# SignalConditioningShield.net
KiCad netlist of a schematic drawn in Altium Designer
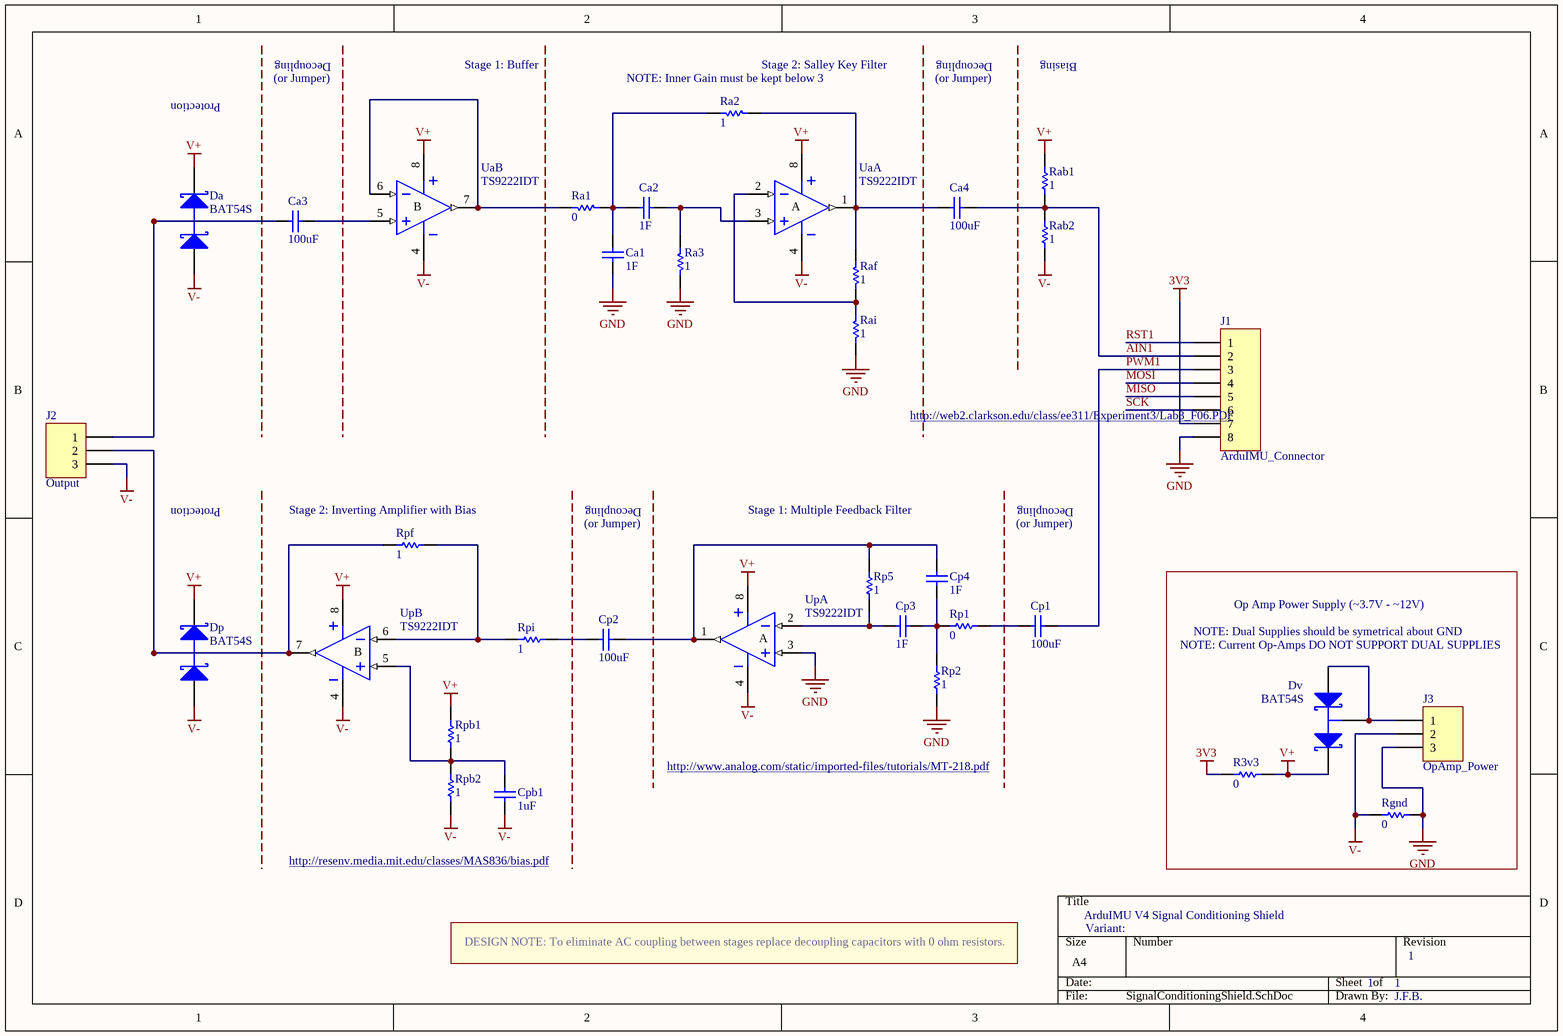
[diagram p0: SignalConditioningShield.SchDoc]

(export (version "E")
  (design (tool "Eeschema 10.0.6"))
  (components
    (comp (ref "Ca1")
      (value "1F")
      (footprint "8-1206")
      (description "Capacitor (Semiconductor SIM Model)")
      (fields (field (name "Comment") "Cap Semi") (field (name "PUBLISHER") "Altium Limited"))
      (libsource (lib "Miscellaneous Devices") (part "Cap Semi"))
    )
    (comp (ref "Ca2")
      (value "1F")
      (footprint "8-1206")
      (description "Capacitor (Semiconductor SIM Model)")
      (fields (field (name "Comment") "Cap Semi") (field (name "PUBLISHER") "Altium Limited"))
      (libsource (lib "Miscellaneous Devices") (part "Cap Semi"))
    )
    (comp (ref "Ca3")
      (value "100uF")
      (footprint "8-1206")
      (description "Capacitor (Semiconductor SIM Model)")
      (fields (field (name "Comment") "Cap Semi") (field (name "PUBLISHER") "Altium Limited"))
      (libsource (lib "Miscellaneous Devices") (part "Cap Semi"))
    )
    (comp (ref "Ca4")
      (value "100uF")
      (footprint "8-1206")
      (description "Capacitor (Semiconductor SIM Model)")
      (fields (field (name "Comment") "Cap Semi") (field (name "PUBLISHER") "Altium Limited"))
      (libsource (lib "Miscellaneous Devices") (part "Cap Semi"))
    )
    (comp (ref "Cp1")
      (value "100uF")
      (footprint "8-1206")
      (description "Capacitor (Semiconductor SIM Model)")
      (fields (field (name "Comment") "Cap Semi") (field (name "PUBLISHER") "Altium Limited"))
      (libsource (lib "Miscellaneous Devices") (part "Cap Semi"))
    )
    (comp (ref "Cp2")
      (value "100uF")
      (footprint "8-1206")
      (description "Capacitor (Semiconductor SIM Model)")
      (fields (field (name "Comment") "Cap Semi") (field (name "PUBLISHER") "Altium Limited"))
      (libsource (lib "Miscellaneous Devices") (part "Cap Semi"))
    )
    (comp (ref "Cp3")
      (value "1F")
      (footprint "8-1206")
      (description "Capacitor (Semiconductor SIM Model)")
      (fields (field (name "Comment") "Cap Semi") (field (name "PUBLISHER") "Altium Limited"))
      (libsource (lib "Miscellaneous Devices") (part "Cap Semi"))
    )
    (comp (ref "Cp4")
      (value "1F")
      (footprint "8-1206")
      (description "Capacitor (Semiconductor SIM Model)")
      (fields (field (name "Comment") "Cap Semi") (field (name "PUBLISHER") "Altium Limited"))
      (libsource (lib "Miscellaneous Devices") (part "Cap Semi"))
    )
    (comp (ref "Cpb1")
      (value "1uF")
      (footprint "8-1206")
      (description "Capacitor (Semiconductor SIM Model)")
      (fields (field (name "Comment") "Cap Semi") (field (name "PUBLISHER") "Altium Limited"))
      (libsource (lib "Miscellaneous Devices") (part "Cap Semi"))
    )
    (comp (ref "Da")
      (value "BAT54S")
      (footprint "SOT23_M")
      (description "Schottky Barrier Double Diode")
      (fields (field (name "PUBLISHER") "Altium Limited"))
      (libsource (lib "Philips Discrete Diode - Schottky") (part "BAT54S"))
    )
    (comp (ref "Dp")
      (value "BAT54S")
      (footprint "SOT23_M")
      (description "Schottky Barrier Double Diode")
      (fields (field (name "PUBLISHER") "Altium Limited"))
      (libsource (lib "Philips Discrete Diode - Schottky") (part "BAT54S"))
    )
    (comp (ref "Dv")
      (value "BAT54S")
      (footprint "SOT23_M")
      (description "Schottky Barrier Double Diode")
      (fields (field (name "PUBLISHER") "Altium Limited"))
      (libsource (lib "Philips Discrete Diode - Schottky") (part "BAT54S"))
    )
    (comp (ref "J1")
      (value "ArduIMU_Connector")
      (footprint "HDR1X8")
      (description "Header, 8-Pin")
      (fields (field (name "PUBLISHER") "Altium Limited"))
      (libsource (lib "Miscellaneous Connectors") (part "Header 8"))
    )
    (comp (ref "J2")
      (value "Output")
      (footprint "HDR1X3")
      (description "Header, 3-Pin")
      (fields (field (name "PUBLISHER") "Altium Limited"))
      (libsource (lib "Miscellaneous Connectors") (part "Header 3"))
    )
    (comp (ref "J3")
      (value "OpAmp_Power")
      (footprint "HDR1X3")
      (description "Header, 3-Pin")
      (fields (field (name "PUBLISHER") "Altium Limited"))
      (libsource (lib "") (part "Header 3_1"))
    )
    (comp (ref "R3v3")
      (value "0")
      (footprint "6-0805")
      (description "Thick Film Chip Resistor, 1 Ohm to 10M Ohm Range, 5% Tolerance, 0805 Size, 0.125 W")
      (fields (field (name "PUBLISHER") "Altium Limited"))
      (libsource (lib "Panasonic Resistor") (part "ERJ6GE"))
    )
    (comp (ref "Ra1")
      (value "0")
      (footprint "8-1206")
      (description "Precision Thick Film Chip Resistor, 10 Ohm to 2.2M Ohm Range, 1% Tolerance, 1206 Size, 0.125 W")
      (fields (field (name "PUBLISHER") "Altium Limited"))
      (libsource (lib "Panasonic Resistor") (part "ERJ8EN"))
    )
    (comp (ref "Ra2")
      (value "1")
      (footprint "8-1206")
      (description "Precision Thick Film Chip Resistor, 10 Ohm to 2.2M Ohm Range, 1% Tolerance, 1206 Size, 0.125 W")
      (fields (field (name "PUBLISHER") "Altium Limited"))
      (libsource (lib "Panasonic Resistor") (part "ERJ8EN"))
    )
    (comp (ref "Ra3")
      (value "1")
      (footprint "8-1206")
      (description "Precision Thick Film Chip Resistor, 10 Ohm to 2.2M Ohm Range, 1% Tolerance, 1206 Size, 0.125 W")
      (fields (field (name "PUBLISHER") "Altium Limited"))
      (libsource (lib "Panasonic Resistor") (part "ERJ8EN"))
    )
    (comp (ref "Rab1")
      (value "1")
      (footprint "8-1206")
      (description "Precision Thick Film Chip Resistor, 10 Ohm to 2.2M Ohm Range, 1% Tolerance, 1206 Size, 0.125 W")
      (fields (field (name "PUBLISHER") "Altium Limited"))
      (libsource (lib "Panasonic Resistor") (part "ERJ8EN"))
    )
    (comp (ref "Rab2")
      (value "1")
      (footprint "8-1206")
      (description "Precision Thick Film Chip Resistor, 10 Ohm to 2.2M Ohm Range, 1% Tolerance, 1206 Size, 0.125 W")
      (fields (field (name "PUBLISHER") "Altium Limited"))
      (libsource (lib "Panasonic Resistor") (part "ERJ8EN"))
    )
    (comp (ref "Raf")
      (value "1")
      (footprint "8-1206")
      (description "Precision Thick Film Chip Resistor, 10 Ohm to 2.2M Ohm Range, 1% Tolerance, 1206 Size, 0.125 W")
      (fields (field (name "PUBLISHER") "Altium Limited"))
      (libsource (lib "Panasonic Resistor") (part "ERJ8EN"))
    )
    (comp (ref "Rai")
      (value "1")
      (footprint "8-1206")
      (description "Precision Thick Film Chip Resistor, 10 Ohm to 2.2M Ohm Range, 1% Tolerance, 1206 Size, 0.125 W")
      (fields (field (name "PUBLISHER") "Altium Limited"))
      (libsource (lib "Panasonic Resistor") (part "ERJ8EN"))
    )
    (comp (ref "Rgnd")
      (value "0")
      (footprint "6-0805")
      (description "Thick Film Chip Resistor, 1 Ohm to 10M Ohm Range, 5% Tolerance, 0805 Size, 0.125 W")
      (fields (field (name "PUBLISHER") "Altium Limited"))
      (libsource (lib "Panasonic Resistor") (part "ERJ6GE"))
    )
    (comp (ref "Rp1")
      (value "0")
      (footprint "8-1206")
      (description "Precision Thick Film Chip Resistor, 10 Ohm to 2.2M Ohm Range, 1% Tolerance, 1206 Size, 0.125 W")
      (fields (field (name "PUBLISHER") "Altium Limited"))
      (libsource (lib "Panasonic Resistor") (part "ERJ8EN"))
    )
    (comp (ref "Rp2")
      (value "1")
      (footprint "8-1206")
      (description "Precision Thick Film Chip Resistor, 10 Ohm to 2.2M Ohm Range, 1% Tolerance, 1206 Size, 0.125 W")
      (fields (field (name "PUBLISHER") "Altium Limited"))
      (libsource (lib "Panasonic Resistor") (part "ERJ8EN"))
    )
    (comp (ref "Rp5")
      (value "1")
      (footprint "8-1206")
      (description "Precision Thick Film Chip Resistor, 10 Ohm to 2.2M Ohm Range, 1% Tolerance, 1206 Size, 0.125 W")
      (fields (field (name "PUBLISHER") "Altium Limited"))
      (libsource (lib "Panasonic Resistor") (part "ERJ8EN"))
    )
    (comp (ref "Rpb1")
      (value "1")
      (footprint "8-1206")
      (description "Precision Thick Film Chip Resistor, 10 Ohm to 2.2M Ohm Range, 1% Tolerance, 1206 Size, 0.125 W")
      (fields (field (name "PUBLISHER") "Altium Limited"))
      (libsource (lib "Panasonic Resistor") (part "ERJ8EN"))
    )
    (comp (ref "Rpb2")
      (value "1")
      (footprint "8-1206")
      (description "Precision Thick Film Chip Resistor, 10 Ohm to 2.2M Ohm Range, 1% Tolerance, 1206 Size, 0.125 W")
      (fields (field (name "PUBLISHER") "Altium Limited"))
      (libsource (lib "Panasonic Resistor") (part "ERJ8EN"))
    )
    (comp (ref "Rpf")
      (value "1")
      (footprint "8-1206")
      (description "Precision Thick Film Chip Resistor, 10 Ohm to 2.2M Ohm Range, 1% Tolerance, 1206 Size, 0.125 W")
      (fields (field (name "PUBLISHER") "Altium Limited"))
      (libsource (lib "Panasonic Resistor") (part "ERJ8EN"))
    )
    (comp (ref "Rpi")
      (value "1")
      (footprint "8-1206")
      (description "Precision Thick Film Chip Resistor, 10 Ohm to 2.2M Ohm Range, 1% Tolerance, 1206 Size, 0.125 W")
      (fields (field (name "PUBLISHER") "Altium Limited"))
      (libsource (lib "Panasonic Resistor") (part "ERJ8EN"))
    )
    (comp (ref "Ua")
      (value "TS9222IDT")
      (footprint "TSSOP8_L")
      (description "High precision, high stability dual operational amplifier")
      (libsource (lib "SignalConditioningShield") (part "TS9222IDT"))
    )
    (comp (ref "Up")
      (value "TS9222IDT")
      (footprint "TSSOP8_L")
      (description "High precision, high stability dual operational amplifier")
      (libsource (lib "SignalConditioningShield") (part "TS9222IDT"))
    )
  )
  (nets
    (net (code "1") (name "/AIN1") (class "Default")
      (node (ref "Ca4") (pin "1") (pinfunction "1_1") (pintype "passive"))
      (node (ref "J1") (pin "2") (pinfunction "2_2") (pintype "passive"))
      (node (ref "Rab1") (pin "1") (pinfunction "1_1") (pintype "passive"))
      (node (ref "Rab2") (pin "2") (pinfunction "2_2") (pintype "passive"))
    )
    (net (code "2") (name "/MISO") (class "Default")
      (node (ref "J1") (pin "5") (pinfunction "5_5") (pintype "passive"))
    )
    (net (code "3") (name "/MOSI") (class "Default")
      (node (ref "J1") (pin "4") (pinfunction "4_4") (pintype "passive"))
    )
    (net (code "4") (name "/PWM1") (class "Default")
      (node (ref "Cp1") (pin "2") (pinfunction "2_2") (pintype "passive"))
      (node (ref "J1") (pin "3") (pinfunction "3_3") (pintype "passive"))
    )
    (net (code "5") (name "/RST1") (class "Default")
      (node (ref "J1") (pin "1") (pinfunction "1_1") (pintype "passive"))
    )
    (net (code "6") (name "/SCK") (class "Default")
      (node (ref "J1") (pin "6") (pinfunction "6_6") (pintype "passive"))
    )
    (net (code "7") (name "3V3") (class "Default")
      (node (ref "J1") (pin "7") (pinfunction "7_7") (pintype "passive"))
      (node (ref "R3v3") (pin "2") (pinfunction "2_2") (pintype "passive"))
    )
    (net (code "8") (name "GND") (class "Default")
      (node (ref "Ca1") (pin "1") (pinfunction "1_1") (pintype "passive"))
      (node (ref "J1") (pin "8") (pinfunction "8_8") (pintype "passive"))
      (node (ref "J3") (pin "3") (pinfunction "3_3") (pintype "passive"))
      (node (ref "Ra3") (pin "2") (pinfunction "2_2") (pintype "passive"))
      (node (ref "Rai") (pin "2") (pinfunction "2_2") (pintype "passive"))
      (node (ref "Rgnd") (pin "2") (pinfunction "2_2") (pintype "passive"))
      (node (ref "Rp2") (pin "2") (pinfunction "2_2") (pintype "passive"))
      (node (ref "Up") (pin "3") (pinfunction "IN+_3") (pintype "input"))
    )
    (net (code "9") (name "Net-(Ca1-Pad2)") (class "Default")
      (node (ref "Ca1") (pin "2") (pinfunction "2_2") (pintype "passive"))
      (node (ref "Ca2") (pin "2") (pinfunction "2_2") (pintype "passive"))
      (node (ref "Ra1") (pin "2") (pinfunction "2_2") (pintype "passive"))
      (node (ref "Ra2") (pin "1") (pinfunction "1_1") (pintype "passive"))
    )
    (net (code "10") (name "Net-(Cp1-Pad1)") (class "Default")
      (node (ref "Cp1") (pin "1") (pinfunction "1_1") (pintype "passive"))
      (node (ref "Rp1") (pin "1") (pinfunction "1_1") (pintype "passive"))
    )
    (net (code "11") (name "Net-(Cp2-Pad1)") (class "Default")
      (node (ref "Cp2") (pin "1") (pinfunction "1_1") (pintype "passive"))
      (node (ref "Rpi") (pin "2") (pinfunction "2_2") (pintype "passive"))
    )
    (net (code "12") (name "Net-(Cp3-Pad2)") (class "Default")
      (node (ref "Cp3") (pin "2") (pinfunction "2_2") (pintype "passive"))
      (node (ref "Cp4") (pin "2") (pinfunction "2_2") (pintype "passive"))
      (node (ref "Rp1") (pin "2") (pinfunction "2_2") (pintype "passive"))
      (node (ref "Rp2") (pin "1") (pinfunction "1_1") (pintype "passive"))
    )
    (net (code "13") (name "Net-(Da-C)") (class "Default")
      (node (ref "Ca3") (pin "1") (pinfunction "1_1") (pintype "passive"))
      (node (ref "Da") (pin "3") (pinfunction "C_3") (pintype "passive"))
      (node (ref "J2") (pin "1") (pinfunction "1_1") (pintype "passive"))
    )
    (net (code "14") (name "Net-(Dp-C)") (class "Default")
      (node (ref "Dp") (pin "3") (pinfunction "C_3") (pintype "passive"))
      (node (ref "J2") (pin "2") (pinfunction "2_2") (pintype "passive"))
      (node (ref "Rpf") (pin "2") (pinfunction "2_2") (pintype "passive"))
      (node (ref "Up") (pin "7") (pinfunction "OUT_7") (pintype "output"))
    )
    (net (code "15") (name "Net-(Dv-A)") (class "Default")
      (node (ref "Dv") (pin "1") (pinfunction "A_1") (pintype "passive"))
      (node (ref "Dv") (pin "3") (pinfunction "C_3") (pintype "passive"))
      (node (ref "J3") (pin "1") (pinfunction "1_1") (pintype "passive"))
    )
    (net (code "16") (name "Net-(UaA-IN+)") (class "Default")
      (node (ref "Ca2") (pin "1") (pinfunction "1_1") (pintype "passive"))
      (node (ref "Ra3") (pin "1") (pinfunction "1_1") (pintype "passive"))
      (node (ref "Ua") (pin "3") (pinfunction "IN+_3") (pintype "input"))
    )
    (net (code "17") (name "Net-(UaA-IN-)") (class "Default")
      (node (ref "Raf") (pin "2") (pinfunction "2_2") (pintype "passive"))
      (node (ref "Rai") (pin "1") (pinfunction "1_1") (pintype "passive"))
      (node (ref "Ua") (pin "2") (pinfunction "IN-_2") (pintype "input"))
    )
    (net (code "18") (name "Net-(UaA-OUT)") (class "Default")
      (node (ref "Ca4") (pin "2") (pinfunction "2_2") (pintype "passive"))
      (node (ref "Ra2") (pin "2") (pinfunction "2_2") (pintype "passive"))
      (node (ref "Raf") (pin "1") (pinfunction "1_1") (pintype "passive"))
      (node (ref "Ua") (pin "1") (pinfunction "OUT_1") (pintype "output"))
    )
    (net (code "19") (name "Net-(UaB-IN+)") (class "Default")
      (node (ref "Ca3") (pin "2") (pinfunction "2_2") (pintype "passive"))
      (node (ref "Ua") (pin "5") (pinfunction "IN+_5") (pintype "input"))
    )
    (net (code "20") (name "Net-(UaB-IN-)") (class "Default")
      (node (ref "Ra1") (pin "1") (pinfunction "1_1") (pintype "passive"))
      (node (ref "Ua") (pin "6") (pinfunction "IN-_6") (pintype "input"))
      (node (ref "Ua") (pin "7") (pinfunction "OUT_7") (pintype "output"))
    )
    (net (code "21") (name "Net-(UpA-IN-)") (class "Default")
      (node (ref "Cp3") (pin "1") (pinfunction "1_1") (pintype "passive"))
      (node (ref "Rp5") (pin "1") (pinfunction "1_1") (pintype "passive"))
      (node (ref "Up") (pin "2") (pinfunction "IN-_2") (pintype "input"))
    )
    (net (code "22") (name "Net-(UpA-OUT)") (class "Default")
      (node (ref "Cp2") (pin "2") (pinfunction "2_2") (pintype "passive"))
      (node (ref "Cp4") (pin "1") (pinfunction "1_1") (pintype "passive"))
      (node (ref "Rp5") (pin "2") (pinfunction "2_2") (pintype "passive"))
      (node (ref "Up") (pin "1") (pinfunction "OUT_1") (pintype "output"))
    )
    (net (code "23") (name "Net-(UpB-IN+)") (class "Default")
      (node (ref "Cpb1") (pin "1") (pinfunction "1_1") (pintype "passive"))
      (node (ref "Rpb1") (pin "1") (pinfunction "1_1") (pintype "passive"))
      (node (ref "Rpb2") (pin "2") (pinfunction "2_2") (pintype "passive"))
      (node (ref "Up") (pin "5") (pinfunction "IN+_5") (pintype "input"))
    )
    (net (code "24") (name "Net-(UpB-IN-)") (class "Default")
      (node (ref "Rpf") (pin "1") (pinfunction "1_1") (pintype "passive"))
      (node (ref "Rpi") (pin "1") (pinfunction "1_1") (pintype "passive"))
      (node (ref "Up") (pin "6") (pinfunction "IN-_6") (pintype "input"))
    )
    (net (code "25") (name "V+") (class "Default")
      (node (ref "Da") (pin "2") (pinfunction "K_2") (pintype "passive"))
      (node (ref "Dp") (pin "2") (pinfunction "K_2") (pintype "passive"))
      (node (ref "Dv") (pin "2") (pinfunction "K_2") (pintype "passive"))
      (node (ref "R3v3") (pin "1") (pinfunction "1_1") (pintype "passive"))
      (node (ref "Rab1") (pin "2") (pinfunction "2_2") (pintype "passive"))
      (node (ref "Rpb1") (pin "2") (pinfunction "2_2") (pintype "passive"))
      (node (ref "Ua") (pin "8") (pinfunction "V+_8") (pintype "power_in"))
      (node (ref "Up") (pin "8") (pinfunction "V+_8") (pintype "power_in"))
    )
    (net (code "26") (name "V-") (class "Default")
      (node (ref "Cpb1") (pin "2") (pinfunction "2_2") (pintype "passive"))
      (node (ref "Da") (pin "1") (pinfunction "A_1") (pintype "passive"))
      (node (ref "Dp") (pin "1") (pinfunction "A_1") (pintype "passive"))
      (node (ref "J2") (pin "3") (pinfunction "3_3") (pintype "passive"))
      (node (ref "J3") (pin "2") (pinfunction "2_2") (pintype "passive"))
      (node (ref "Rab2") (pin "1") (pinfunction "1_1") (pintype "passive"))
      (node (ref "Rgnd") (pin "1") (pinfunction "1_1") (pintype "passive"))
      (node (ref "Rpb2") (pin "1") (pinfunction "1_1") (pintype "passive"))
      (node (ref "Ua") (pin "4") (pinfunction "V-_4") (pintype "power_in"))
      (node (ref "Up") (pin "4") (pinfunction "V-_4") (pintype "power_in"))
    )
  )
)
